# box-100-68-esp32.net
KiCad netlist of a schematic drawn in EAGLE
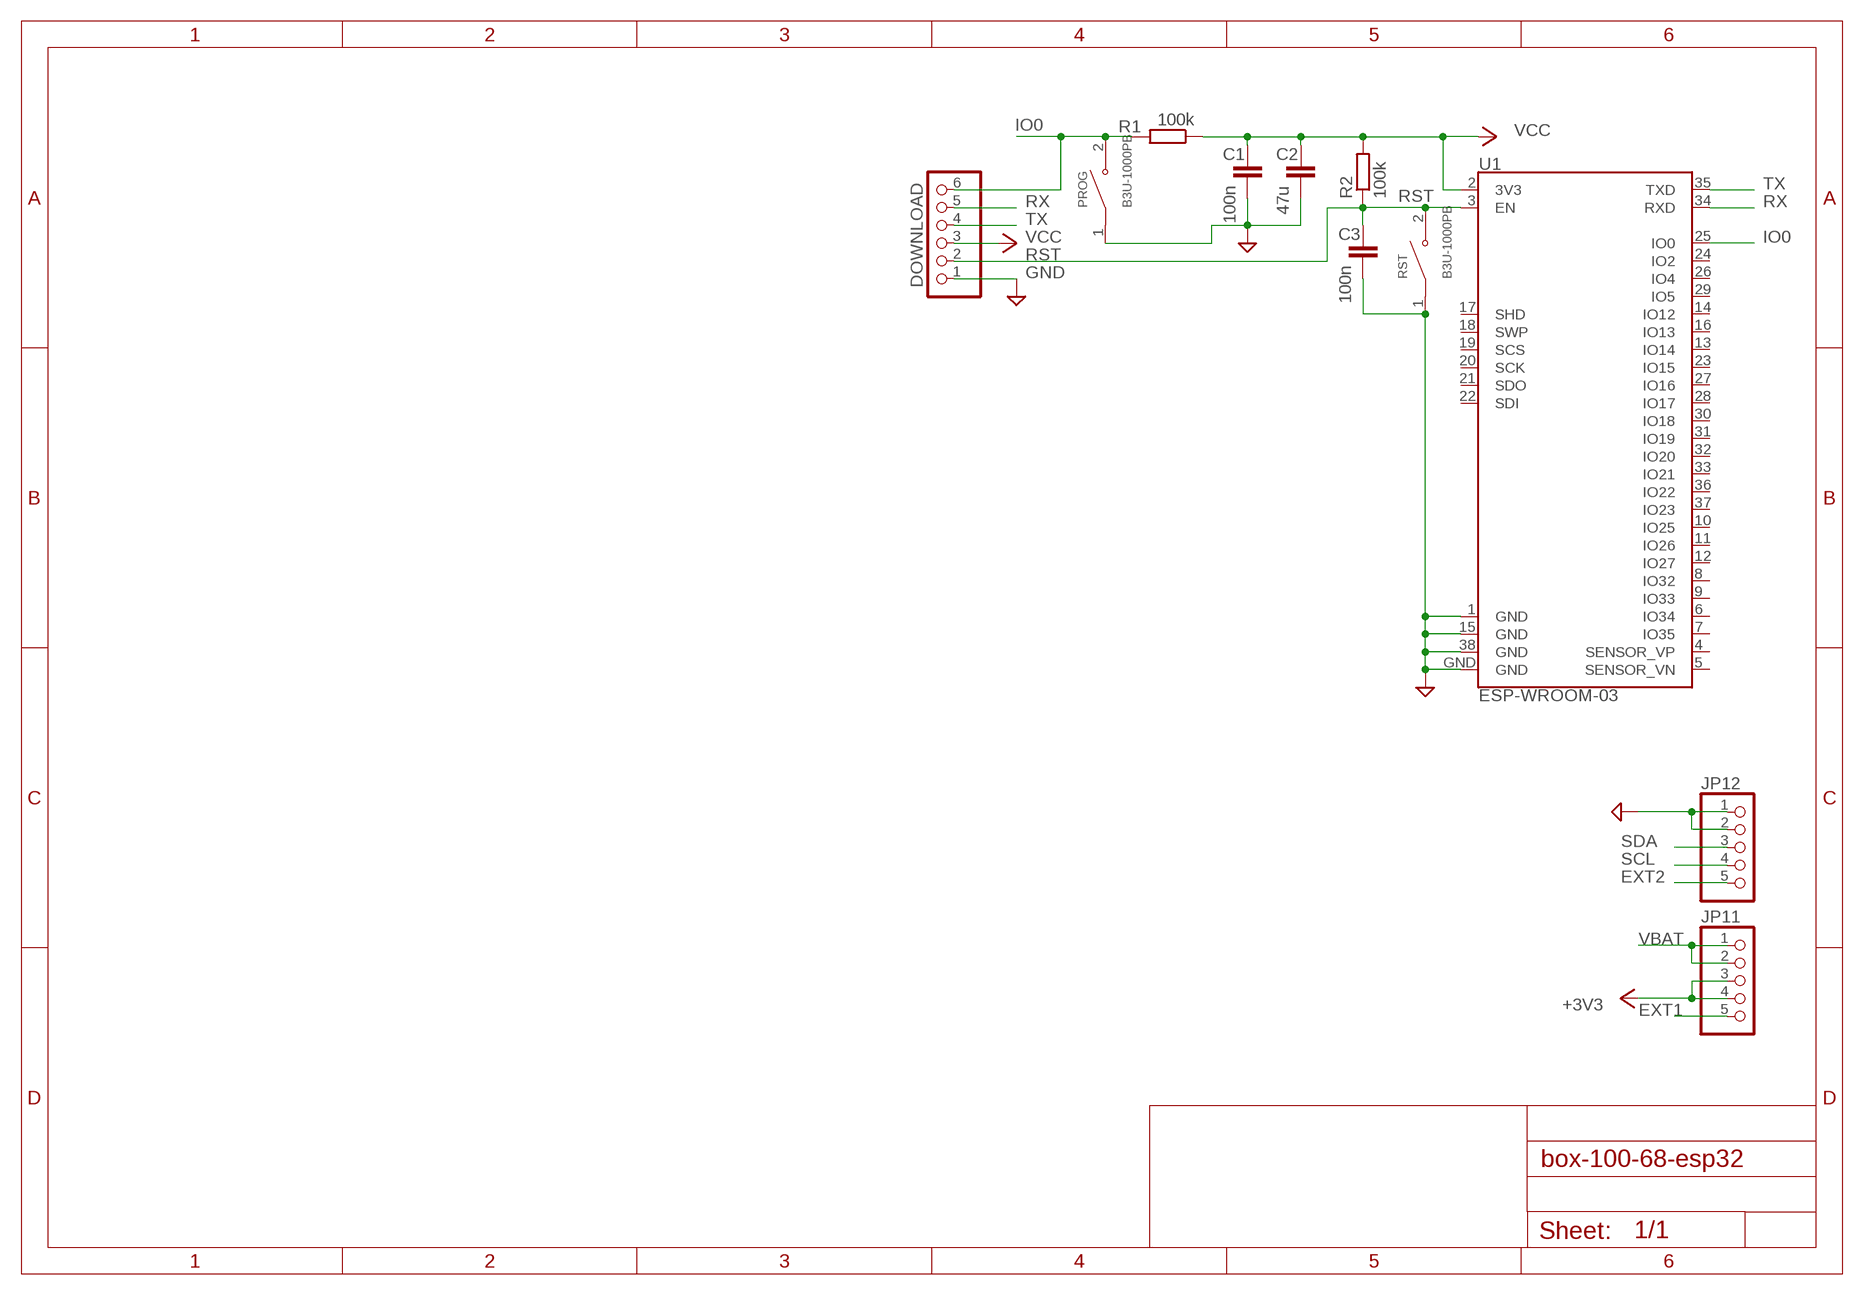
[diagram p0: schematic, sheet 1]

(export (version "E")
  (design (tool "Eeschema 10.0.6"))
  (components
    (comp (ref "C1")
      (value "100n")
      (footprint "eagle-import:C0805")
      (libsource (lib "eagle-import") (part "C"))
    )
    (comp (ref "C2")
      (value "47u")
      (footprint "eagle-import:C0805")
      (libsource (lib "eagle-import") (part "C"))
    )
    (comp (ref "C3")
      (value "100n")
      (footprint "eagle-import:C0805")
      (libsource (lib "eagle-import") (part "C"))
    )
    (comp (ref "DOWNLOAD")
      (value "PINHD-1X6S")
      (footprint "eagle-import:1X06S")
      (libsource (lib "eagle-import") (part "PINHD-1X6S"))
    )
    (comp (ref "JP11")
      (value "PINHD-1X5S")
      (footprint "eagle-import:1X05S")
      (libsource (lib "eagle-import") (part "PINHD-1X5S"))
    )
    (comp (ref "JP12")
      (value "PINHD-1X5S")
      (footprint "eagle-import:1X05S")
      (libsource (lib "eagle-import") (part "PINHD-1X5S"))
    )
    (comp (ref "PROG")
      (value "B3U-1000PB")
      (footprint "eagle-import:SW_B3U-1000PB")
      (libsource (lib "eagle-import") (part "B3U-1000PB"))
    )
    (comp (ref "R1")
      (value "100k")
      (footprint "eagle-import:R1206")
      (libsource (lib "eagle-import") (part "RR1206"))
    )
    (comp (ref "R2")
      (value "100k")
      (footprint "eagle-import:R1206")
      (libsource (lib "eagle-import") (part "RR1206"))
    )
    (comp (ref "RST")
      (value "B3U-1000PB")
      (footprint "eagle-import:SW_B3U-1000PB")
      (libsource (lib "eagle-import") (part "B3U-1000PB"))
    )
    (comp (ref "U1")
      (value "ESP-WROOM-03")
      (footprint "eagle-import:ESP-WROOM-03")
      (libsource (lib "eagle-import") (part "ESP-WROOM-03"))
    )
  )
  (nets
    (net (code "1") (name "+3V3") (class "Default")
      (node (ref "JP11") (pin "3") (pinfunction "3_3") (pintype "passive"))
      (node (ref "JP11") (pin "4") (pinfunction "4_4") (pintype "passive"))
    )
    (net (code "2") (name "/EXT1") (class "Default")
      (node (ref "JP11") (pin "5") (pinfunction "5_5") (pintype "passive"))
    )
    (net (code "3") (name "/EXT2") (class "Default")
      (node (ref "JP12") (pin "5") (pinfunction "5_5") (pintype "passive"))
    )
    (net (code "4") (name "/IO0") (class "Default")
      (node (ref "DOWNLOAD") (pin "6") (pinfunction "6_6") (pintype "passive"))
      (node (ref "PROG") (pin "2") (pinfunction "2_2") (pintype "passive"))
      (node (ref "R1") (pin "2") (pinfunction "2_2") (pintype "passive"))
      (node (ref "U1") (pin "25") (pinfunction "IO0_25") (pintype "bidirectional"))
    )
    (net (code "5") (name "/RST") (class "Default")
      (node (ref "C3") (pin "1") (pinfunction "1_1") (pintype "passive"))
      (node (ref "DOWNLOAD") (pin "2") (pinfunction "2_2") (pintype "passive"))
      (node (ref "R2") (pin "1") (pinfunction "1_1") (pintype "passive"))
      (node (ref "RST") (pin "2") (pinfunction "2_2") (pintype "passive"))
      (node (ref "U1") (pin "3") (pinfunction "EN_3") (pintype "bidirectional"))
    )
    (net (code "6") (name "/RX") (class "Default")
      (node (ref "DOWNLOAD") (pin "5") (pinfunction "5_5") (pintype "passive"))
      (node (ref "U1") (pin "34") (pinfunction "RXD_34") (pintype "bidirectional"))
    )
    (net (code "7") (name "/SCL") (class "Default")
      (node (ref "JP12") (pin "4") (pinfunction "4_4") (pintype "passive"))
    )
    (net (code "8") (name "/SDA") (class "Default")
      (node (ref "JP12") (pin "3") (pinfunction "3_3") (pintype "passive"))
    )
    (net (code "9") (name "/TX") (class "Default")
      (node (ref "DOWNLOAD") (pin "4") (pinfunction "4_4") (pintype "passive"))
      (node (ref "U1") (pin "35") (pinfunction "TXD_35") (pintype "bidirectional"))
    )
    (net (code "10") (name "/VBAT") (class "Default")
      (node (ref "JP11") (pin "1") (pinfunction "1_1") (pintype "passive"))
      (node (ref "JP11") (pin "2") (pinfunction "2_2") (pintype "passive"))
    )
    (net (code "11") (name "GND") (class "Default")
      (node (ref "C1") (pin "2") (pinfunction "2_2") (pintype "passive"))
      (node (ref "C2") (pin "2") (pinfunction "2_2") (pintype "passive"))
      (node (ref "C3") (pin "2") (pinfunction "2_2") (pintype "passive"))
      (node (ref "DOWNLOAD") (pin "1") (pinfunction "1_1") (pintype "passive"))
      (node (ref "JP12") (pin "1") (pinfunction "1_1") (pintype "passive"))
      (node (ref "JP12") (pin "2") (pinfunction "2_2") (pintype "passive"))
      (node (ref "PROG") (pin "1") (pinfunction "1_1") (pintype "passive"))
      (node (ref "RST") (pin "1") (pinfunction "1_1") (pintype "passive"))
      (node (ref "U1") (pin "1") (pinfunction "GND_1") (pintype "bidirectional"))
      (node (ref "U1") (pin "15") (pinfunction "GND_15") (pintype "bidirectional"))
      (node (ref "U1") (pin "38") (pinfunction "GND_38") (pintype "bidirectional"))
      (node (ref "U1") (pin "GND") (pinfunction "GND_GND") (pintype "bidirectional"))
    )
    (net (code "12") (name "VCC") (class "Default")
      (node (ref "C1") (pin "1") (pinfunction "1_1") (pintype "passive"))
      (node (ref "C2") (pin "1") (pinfunction "1_1") (pintype "passive"))
      (node (ref "DOWNLOAD") (pin "3") (pinfunction "3_3") (pintype "passive"))
      (node (ref "R1") (pin "1") (pinfunction "1_1") (pintype "passive"))
      (node (ref "R2") (pin "2") (pinfunction "2_2") (pintype "passive"))
      (node (ref "U1") (pin "2") (pinfunction "3V3_2") (pintype "bidirectional"))
    )
    (net (code "13") (name "unconnected-(U1-IO2-Pad24)") (class "Default")
      (node (ref "U1") (pin "24") (pinfunction "IO2_24") (pintype "bidirectional"))
    )
    (net (code "14") (name "unconnected-(U1-IO4-Pad26)") (class "Default")
      (node (ref "U1") (pin "26") (pinfunction "IO4_26") (pintype "bidirectional"))
    )
    (net (code "15") (name "unconnected-(U1-IO5-Pad29)") (class "Default")
      (node (ref "U1") (pin "29") (pinfunction "IO5_29") (pintype "bidirectional"))
    )
    (net (code "16") (name "unconnected-(U1-IO12-Pad14)") (class "Default")
      (node (ref "U1") (pin "14") (pinfunction "IO12_14") (pintype "bidirectional"))
    )
    (net (code "17") (name "unconnected-(U1-IO13-Pad16)") (class "Default")
      (node (ref "U1") (pin "16") (pinfunction "IO13_16") (pintype "bidirectional"))
    )
    (net (code "18") (name "unconnected-(U1-IO14-Pad13)") (class "Default")
      (node (ref "U1") (pin "13") (pinfunction "IO14_13") (pintype "bidirectional"))
    )
    (net (code "19") (name "unconnected-(U1-IO15-Pad23)") (class "Default")
      (node (ref "U1") (pin "23") (pinfunction "IO15_23") (pintype "bidirectional"))
    )
    (net (code "20") (name "unconnected-(U1-IO16-Pad27)") (class "Default")
      (node (ref "U1") (pin "27") (pinfunction "IO16_27") (pintype "bidirectional"))
    )
    (net (code "21") (name "unconnected-(U1-IO17-Pad28)") (class "Default")
      (node (ref "U1") (pin "28") (pinfunction "IO17_28") (pintype "bidirectional"))
    )
    (net (code "22") (name "unconnected-(U1-IO18-Pad30)") (class "Default")
      (node (ref "U1") (pin "30") (pinfunction "IO18_30") (pintype "bidirectional"))
    )
    (net (code "23") (name "unconnected-(U1-IO19-Pad31)") (class "Default")
      (node (ref "U1") (pin "31") (pinfunction "IO19_31") (pintype "bidirectional"))
    )
    (net (code "24") (name "unconnected-(U1-IO20-Pad32)") (class "Default")
      (node (ref "U1") (pin "32") (pinfunction "IO20_32") (pintype "bidirectional"))
    )
    (net (code "25") (name "unconnected-(U1-IO21-Pad33)") (class "Default")
      (node (ref "U1") (pin "33") (pinfunction "IO21_33") (pintype "bidirectional"))
    )
    (net (code "26") (name "unconnected-(U1-IO22-Pad36)") (class "Default")
      (node (ref "U1") (pin "36") (pinfunction "IO22_36") (pintype "bidirectional"))
    )
    (net (code "27") (name "unconnected-(U1-IO23-Pad37)") (class "Default")
      (node (ref "U1") (pin "37") (pinfunction "IO23_37") (pintype "bidirectional"))
    )
    (net (code "28") (name "unconnected-(U1-IO25-Pad10)") (class "Default")
      (node (ref "U1") (pin "10") (pinfunction "IO25_10") (pintype "bidirectional"))
    )
    (net (code "29") (name "unconnected-(U1-IO26-Pad11)") (class "Default")
      (node (ref "U1") (pin "11") (pinfunction "IO26_11") (pintype "bidirectional"))
    )
    (net (code "30") (name "unconnected-(U1-IO27-Pad12)") (class "Default")
      (node (ref "U1") (pin "12") (pinfunction "IO27_12") (pintype "bidirectional"))
    )
    (net (code "31") (name "unconnected-(U1-IO32-Pad8)") (class "Default")
      (node (ref "U1") (pin "8") (pinfunction "IO32_8") (pintype "bidirectional"))
    )
    (net (code "32") (name "unconnected-(U1-IO33-Pad9)") (class "Default")
      (node (ref "U1") (pin "9") (pinfunction "IO33_9") (pintype "bidirectional"))
    )
    (net (code "33") (name "unconnected-(U1-IO34-Pad6)") (class "Default")
      (node (ref "U1") (pin "6") (pinfunction "IO34_6") (pintype "bidirectional"))
    )
    (net (code "34") (name "unconnected-(U1-IO35-Pad7)") (class "Default")
      (node (ref "U1") (pin "7") (pinfunction "IO35_7") (pintype "bidirectional"))
    )
    (net (code "35") (name "unconnected-(U1-SCK-Pad20)") (class "Default")
      (node (ref "U1") (pin "20") (pinfunction "SCK_20") (pintype "bidirectional"))
    )
    (net (code "36") (name "unconnected-(U1-SCS-Pad19)") (class "Default")
      (node (ref "U1") (pin "19") (pinfunction "SCS_19") (pintype "bidirectional"))
    )
    (net (code "37") (name "unconnected-(U1-SDI-Pad22)") (class "Default")
      (node (ref "U1") (pin "22") (pinfunction "SDI_22") (pintype "bidirectional"))
    )
    (net (code "38") (name "unconnected-(U1-SDO-Pad21)") (class "Default")
      (node (ref "U1") (pin "21") (pinfunction "SDO_21") (pintype "bidirectional"))
    )
    (net (code "39") (name "unconnected-(U1-SENSOR_VN-Pad5)") (class "Default")
      (node (ref "U1") (pin "5") (pinfunction "SENSOR_VN_5") (pintype "bidirectional"))
    )
    (net (code "40") (name "unconnected-(U1-SENSOR_VP-Pad4)") (class "Default")
      (node (ref "U1") (pin "4") (pinfunction "SENSOR_VP_4") (pintype "bidirectional"))
    )
    (net (code "41") (name "unconnected-(U1-SHD-Pad17)") (class "Default")
      (node (ref "U1") (pin "17") (pinfunction "SHD_17") (pintype "bidirectional"))
    )
    (net (code "42") (name "unconnected-(U1-SWP-Pad18)") (class "Default")
      (node (ref "U1") (pin "18") (pinfunction "SWP_18") (pintype "bidirectional"))
    )
  )
)
